# 01_MAIN.net
KiCad netlist of a schematic drawn in Altium Designer
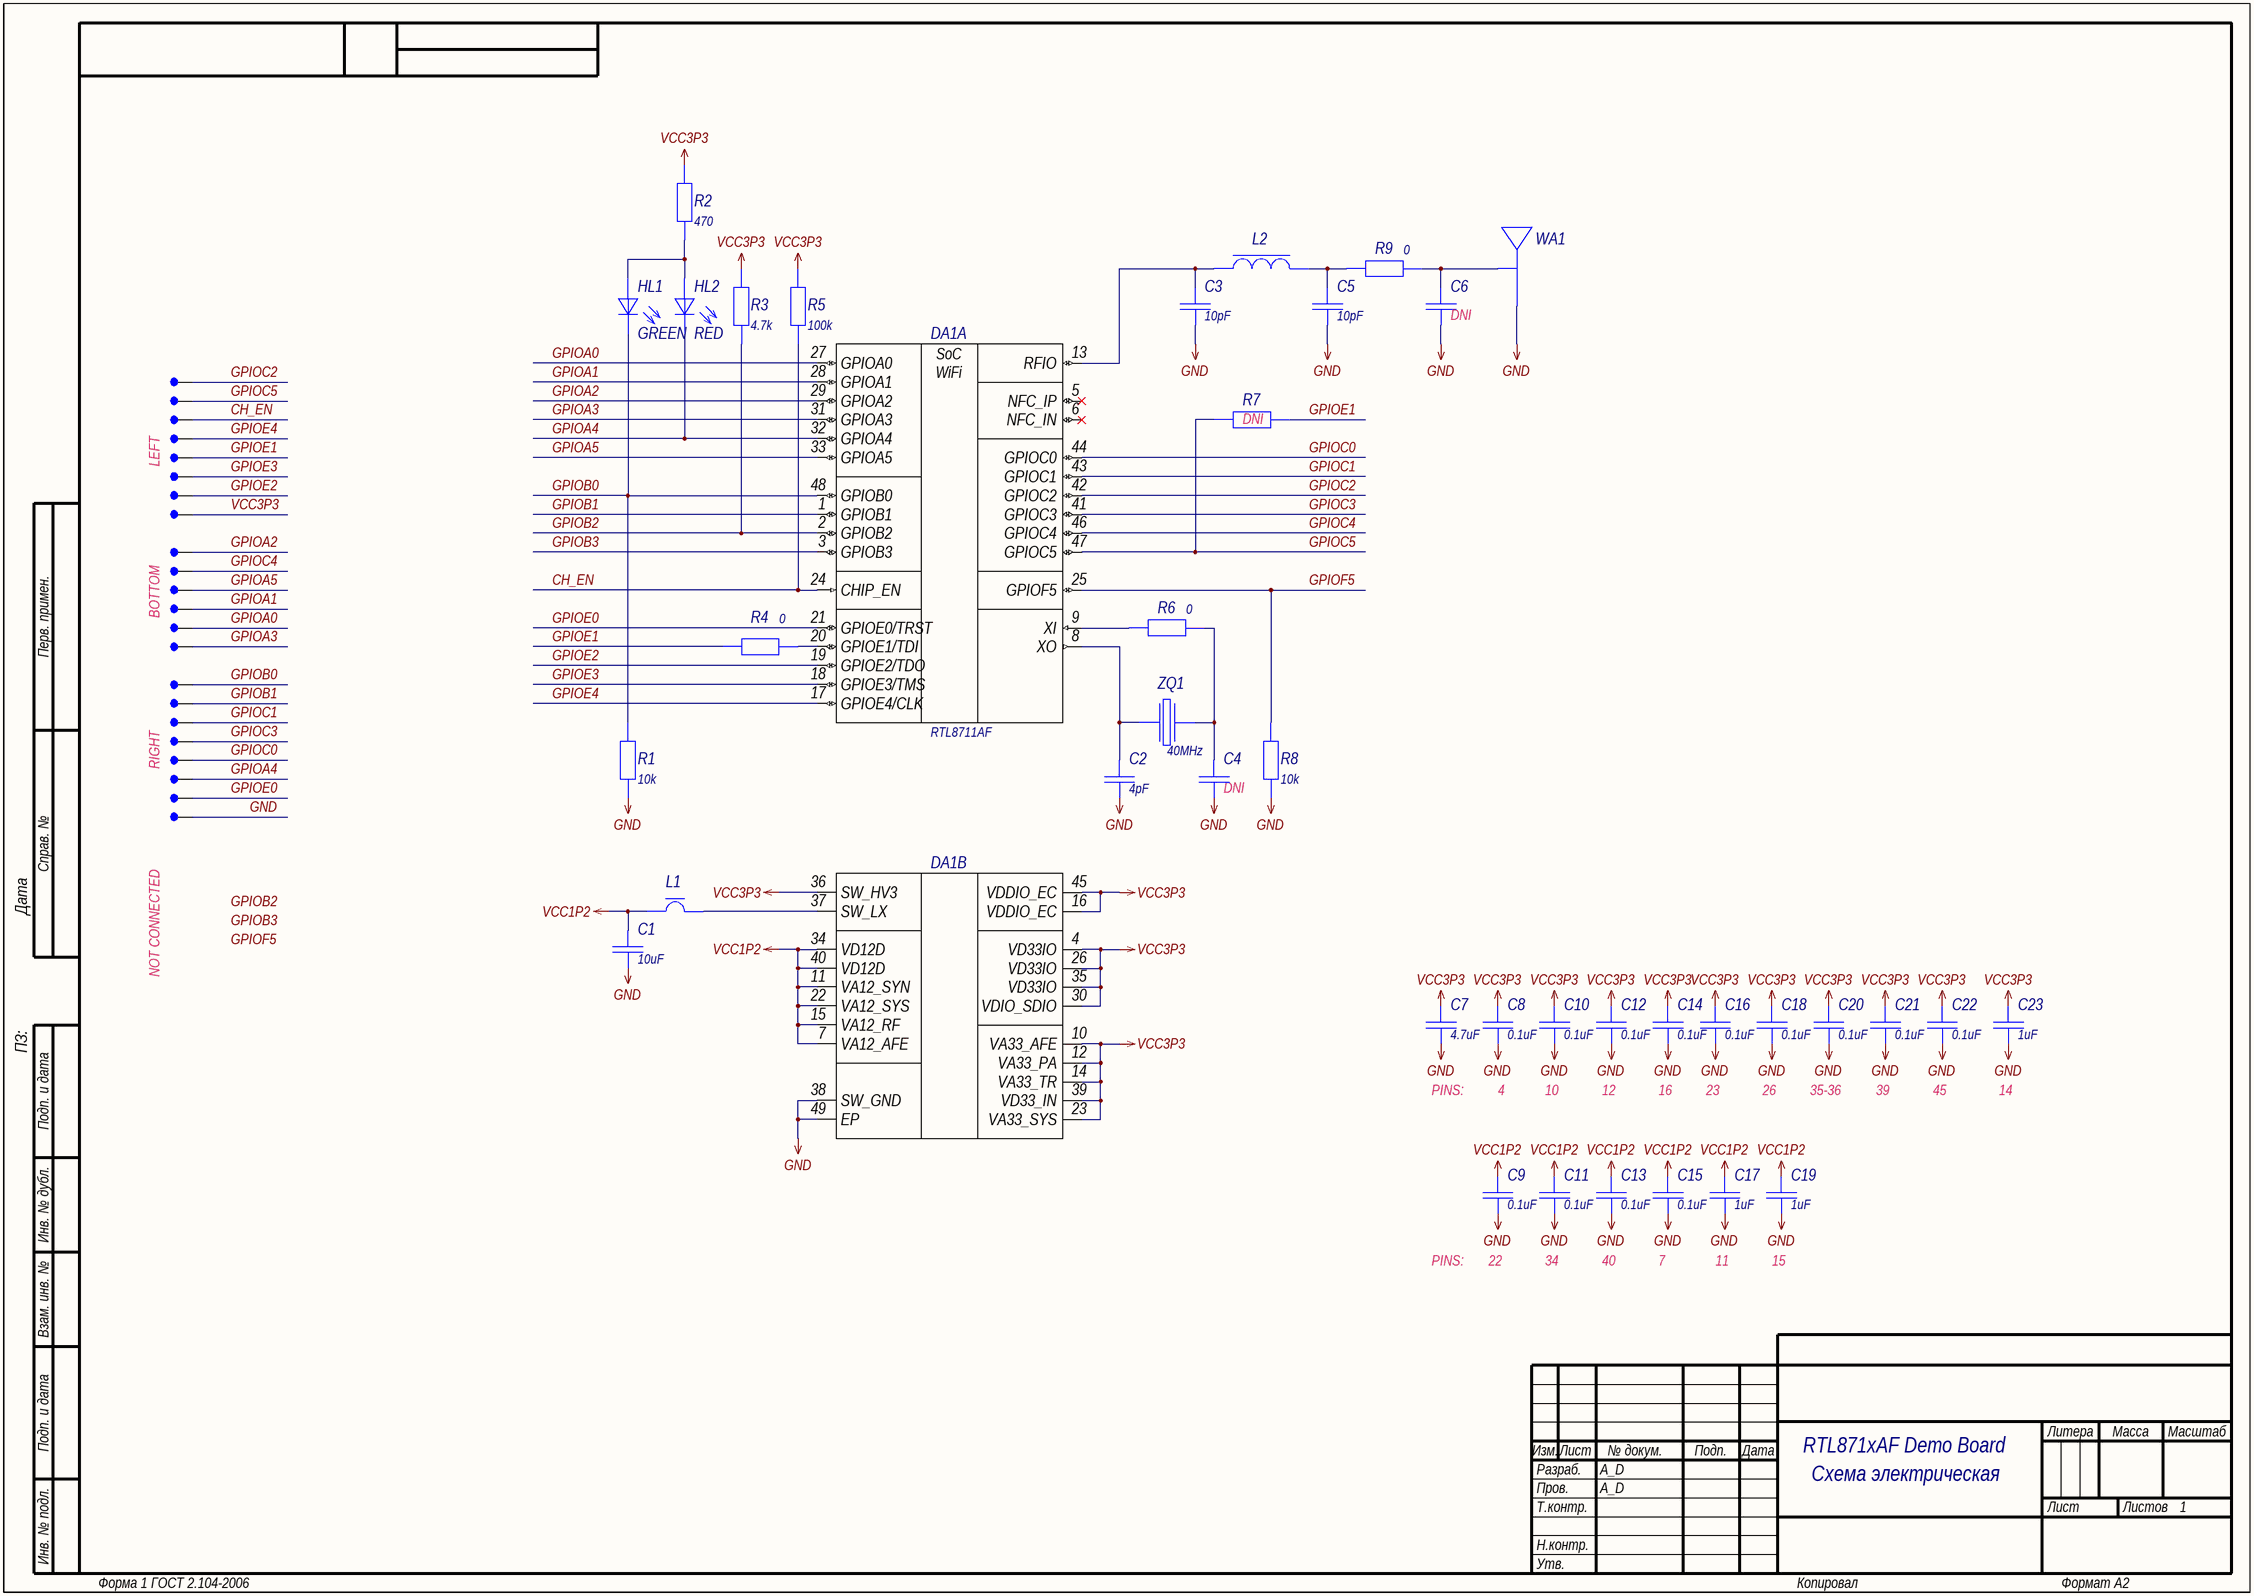
[diagram p0: 01_MAIN.SchDoc]

(export (version "E")
  (design (tool "Eeschema 10.0.6"))
  (components
    (comp (ref "C1")
      (value "10uF")
      (footprint "C0603_L")
      (fields
        (field (name "PART NUMBER") "GRM188R60J106ME47D")
        (field (name "VOLTAGE") "6.3V")
        (field (name "TOLERANCE") "±20%")
        (field (name "PUBLISHER") "Andrew Danich")
      )
      (libsource (lib "Lib_IMP_GOST") (part "Capacitor"))
    )
    (comp (ref "C2")
      (value "4pF")
      (footprint "C0402_L")
      (fields
        (field (name "PART NUMBER") "GRM1555C1H4R0CZ01D")
        (field (name "VOLTAGE") "50V")
        (field (name "TOLERANCE") "±0.25pF")
        (field (name "PUBLISHER") "Andrew Danich")
      )
      (libsource (lib "Lib_IMP_GOST") (part "Capacitor"))
    )
    (comp (ref "C3")
      (value "10pF")
      (footprint "C0402_L")
      (fields
        (field (name "PART NUMBER") "GRM1555C1H100JA01D")
        (field (name "VOLTAGE") "50V")
        (field (name "TOLERANCE") "±5%")
        (field (name "PUBLISHER") "Andrew Danich")
      )
      (libsource (lib "Lib_IMP_GOST") (part "Capacitor"))
    )
    (comp (ref "C4")
      (value "Capacitor")
      (footprint "C0402_L")
      (fields
        (field (name "PART NUMBER") "GRM1555C1H4R0CZ01D")
        (field (name "VOLTAGE") "50V")
        (field (name "TOLERANCE") "±0.25pF")
        (field (name "PUBLISHER") "Andrew Danich")
      )
      (libsource (lib "Lib_IMP_GOST") (part "Capacitor"))
    )
    (comp (ref "C5")
      (value "10pF")
      (footprint "C0402_L")
      (fields
        (field (name "PART NUMBER") "GRM1555C1H100JA01D")
        (field (name "VOLTAGE") "50V")
        (field (name "TOLERANCE") "±5%")
        (field (name "PUBLISHER") "Andrew Danich")
      )
      (libsource (lib "Lib_IMP_GOST") (part "Capacitor"))
    )
    (comp (ref "C6")
      (value "Capacitor")
      (footprint "C0402_L")
      (fields
        (field (name "PART NUMBER") "GRM1555C1H100JA01D")
        (field (name "VOLTAGE") "50V")
        (field (name "TOLERANCE") "±5%")
        (field (name "PUBLISHER") "Andrew Danich")
      )
      (libsource (lib "Lib_IMP_GOST") (part "Capacitor"))
    )
    (comp (ref "C7")
      (value "4.7uF")
      (footprint "C0603_L")
      (fields
        (field (name "PART NUMBER") "GRM188R61A475KE15D")
        (field (name "VOLTAGE") "10V")
        (field (name "TOLERANCE") "±10%")
        (field (name "PUBLISHER") "Andrew Danich")
      )
      (libsource (lib "Lib_IMP_GOST") (part "Capacitor"))
    )
    (comp (ref "C8")
      (value "0.1uF")
      (footprint "C0402_L")
      (fields
        (field (name "PART NUMBER") "GRM155R71A104KA01D")
        (field (name "VOLTAGE") "10V")
        (field (name "TOLERANCE") "±10%")
        (field (name "PUBLISHER") "Andrew Danich")
      )
      (libsource (lib "Lib_IMP_GOST") (part "Capacitor"))
    )
    (comp (ref "C9")
      (value "0.1uF")
      (footprint "C0402_L")
      (fields
        (field (name "PART NUMBER") "GRM155R71A104KA01D")
        (field (name "VOLTAGE") "10V")
        (field (name "TOLERANCE") "±10%")
        (field (name "PUBLISHER") "Andrew Danich")
      )
      (libsource (lib "Lib_IMP_GOST") (part "Capacitor"))
    )
    (comp (ref "C10")
      (value "0.1uF")
      (footprint "C0402_L")
      (fields
        (field (name "PART NUMBER") "GRM155R71A104KA01D")
        (field (name "VOLTAGE") "10V")
        (field (name "TOLERANCE") "±10%")
        (field (name "PUBLISHER") "Andrew Danich")
      )
      (libsource (lib "Lib_IMP_GOST") (part "Capacitor"))
    )
    (comp (ref "C11")
      (value "0.1uF")
      (footprint "C0402_L")
      (fields
        (field (name "PART NUMBER") "GRM155R71A104KA01D")
        (field (name "VOLTAGE") "10V")
        (field (name "TOLERANCE") "±10%")
        (field (name "PUBLISHER") "Andrew Danich")
      )
      (libsource (lib "Lib_IMP_GOST") (part "Capacitor"))
    )
    (comp (ref "C12")
      (value "0.1uF")
      (footprint "C0402_L")
      (fields
        (field (name "PART NUMBER") "GRM155R71A104KA01D")
        (field (name "VOLTAGE") "10V")
        (field (name "TOLERANCE") "±10%")
        (field (name "PUBLISHER") "Andrew Danich")
      )
      (libsource (lib "Lib_IMP_GOST") (part "Capacitor"))
    )
    (comp (ref "C13")
      (value "0.1uF")
      (footprint "C0402_L")
      (fields
        (field (name "PART NUMBER") "GRM155R71A104KA01D")
        (field (name "VOLTAGE") "10V")
        (field (name "TOLERANCE") "±10%")
        (field (name "PUBLISHER") "Andrew Danich")
      )
      (libsource (lib "Lib_IMP_GOST") (part "Capacitor"))
    )
    (comp (ref "C14")
      (value "0.1uF")
      (footprint "C0402_L")
      (fields
        (field (name "PART NUMBER") "GRM155R71A104KA01D")
        (field (name "VOLTAGE") "10V")
        (field (name "TOLERANCE") "±10%")
        (field (name "PUBLISHER") "Andrew Danich")
      )
      (libsource (lib "Lib_IMP_GOST") (part "Capacitor"))
    )
    (comp (ref "C15")
      (value "0.1uF")
      (footprint "C0402_L")
      (fields
        (field (name "PART NUMBER") "GRM155R71A104KA01D")
        (field (name "VOLTAGE") "10V")
        (field (name "TOLERANCE") "±10%")
        (field (name "PUBLISHER") "Andrew Danich")
      )
      (libsource (lib "Lib_IMP_GOST") (part "Capacitor"))
    )
    (comp (ref "C16")
      (value "0.1uF")
      (footprint "C0402_L")
      (fields
        (field (name "PART NUMBER") "GRM155R71A104KA01D")
        (field (name "VOLTAGE") "10V")
        (field (name "TOLERANCE") "±10%")
        (field (name "PUBLISHER") "Andrew Danich")
      )
      (libsource (lib "Lib_IMP_GOST") (part "Capacitor"))
    )
    (comp (ref "C17")
      (value "1uF")
      (footprint "C0402_L")
      (fields
        (field (name "PART NUMBER") "GRM155R61A105KE15D")
        (field (name "VOLTAGE") "10V")
        (field (name "TOLERANCE") "±10%")
        (field (name "PUBLISHER") "Andrew Danich")
      )
      (libsource (lib "Lib_IMP_GOST") (part "Capacitor"))
    )
    (comp (ref "C18")
      (value "0.1uF")
      (footprint "C0402_L")
      (fields
        (field (name "PART NUMBER") "GRM155R71A104KA01D")
        (field (name "VOLTAGE") "10V")
        (field (name "TOLERANCE") "±10%")
        (field (name "PUBLISHER") "Andrew Danich")
      )
      (libsource (lib "Lib_IMP_GOST") (part "Capacitor"))
    )
    (comp (ref "C19")
      (value "1uF")
      (footprint "C0402_L")
      (fields
        (field (name "PART NUMBER") "GRM155R61A105KE15D")
        (field (name "VOLTAGE") "10V")
        (field (name "TOLERANCE") "±10%")
        (field (name "PUBLISHER") "Andrew Danich")
      )
      (libsource (lib "Lib_IMP_GOST") (part "Capacitor"))
    )
    (comp (ref "C20")
      (value "0.1uF")
      (footprint "C0402_L")
      (fields
        (field (name "PART NUMBER") "GRM155R71A104KA01D")
        (field (name "VOLTAGE") "10V")
        (field (name "TOLERANCE") "±10%")
        (field (name "PUBLISHER") "Andrew Danich")
      )
      (libsource (lib "Lib_IMP_GOST") (part "Capacitor"))
    )
    (comp (ref "C21")
      (value "0.1uF")
      (footprint "C0402_L")
      (fields
        (field (name "PART NUMBER") "GRM155R71A104KA01D")
        (field (name "VOLTAGE") "10V")
        (field (name "TOLERANCE") "±10%")
        (field (name "PUBLISHER") "Andrew Danich")
      )
      (libsource (lib "Lib_IMP_GOST") (part "Capacitor"))
    )
    (comp (ref "C22")
      (value "0.1uF")
      (footprint "C0402_L")
      (fields
        (field (name "PART NUMBER") "GRM155R71A104KA01D")
        (field (name "VOLTAGE") "10V")
        (field (name "TOLERANCE") "±10%")
        (field (name "PUBLISHER") "Andrew Danich")
      )
      (libsource (lib "Lib_IMP_GOST") (part "Capacitor"))
    )
    (comp (ref "C23")
      (value "1uF")
      (footprint "C0402_L")
      (fields
        (field (name "PART NUMBER") "GRM155R61A105KE15D")
        (field (name "VOLTAGE") "10V")
        (field (name "TOLERANCE") "±10%")
        (field (name "PUBLISHER") "Andrew Danich")
      )
      (libsource (lib "Lib_IMP_GOST") (part "Capacitor"))
    )
    (comp (ref "DA1")
      (value "RTL8711AF")
      (footprint "QFN-48-6x6")
      (fields
        (field (name "MANUFACTURER") "Realtek")
        (field (name "Comment") "RTL871xAF")
        (field (name "PART NUMBER") "RTL8711AF")
        (field (name "PUBLISHER") "Andrew Danich")
      )
      (libsource (lib "Lib_IMP_GOST") (part "RTL871xAF"))
    )
    (comp (ref "HL1")
      (value "GREEN")
      (footprint "LD0402_L")
      (fields
        (field (name "PART NUMBER") "KPHHS-1005MGCK")
        (field (name "MANUFACTURER") "Kingbright")
        (field (name "PUBLISHER") "Andrew Danich")
      )
      (libsource (lib "Lib_IMP_GOST") (part "Led-1"))
    )
    (comp (ref "HL2")
      (value "RED")
      (footprint "LD0402_L")
      (fields
        (field (name "PART NUMBER") "KPHHS-1005QBC-D-V")
        (field (name "MANUFACTURER") "Kingbright")
        (field (name "PUBLISHER") "Andrew Danich")
      )
      (libsource (lib "Lib_IMP_GOST") (part "Led-1"))
    )
    (comp (ref "L1")
      (value "FerriteBead")
      (footprint "L0805_L")
      (fields
        (field (name "PART NUMBER") "BLM21PG331SN1")
        (field (name "MANUFACTURER") "Murata")
        (field (name "PUBLISHER") "Andrew Danich")
      )
      (libsource (lib "Lib_IMP_GOST") (part "FerriteBead"))
    )
    (comp (ref "L2")
      (value "Coil")
      (footprint "L0402_L")
      (fields
        (field (name "PART NUMBER") "LQG15HS2N2S02D")
        (field (name "TOLERANCE") "±0.3nH")
        (field (name "MANUFACTURER") "Murata")
        (field (name "PUBLISHER") "Andrew Danich")
      )
      (libsource (lib "Lib_IMP_GOST") (part "Coil"))
    )
    (comp (ref "R1")
      (value "10k")
      (footprint "R0402_L")
      (fields
        (field (name "PART NUMBER") "RC0402FR-0710KL")
        (field (name "TOLERANCE") "±1%")
        (field (name "MANUFACTURER") "Yageo")
        (field (name "PUBLISHER") "Andrew Danich")
      )
      (libsource (lib "Lib_IMP_GOST") (part "Resistor"))
    )
    (comp (ref "R2")
      (value "470")
      (footprint "R0402_L")
      (fields
        (field (name "PART NUMBER") "RC0402JR-07430RL")
        (field (name "TOLERANCE") "±5%")
        (field (name "MANUFACTURER") "Yageo")
        (field (name "PUBLISHER") "Andrew Danich")
      )
      (libsource (lib "Lib_IMP_GOST") (part "Resistor"))
    )
    (comp (ref "R3")
      (value "4.7k")
      (footprint "R0402_L")
      (fields
        (field (name "PART NUMBER") "RC0402JR-074K7L")
        (field (name "TOLERANCE") "±5%")
        (field (name "MANUFACTURER") "Yageo")
        (field (name "PUBLISHER") "Andrew Danich")
      )
      (libsource (lib "Lib_IMP_GOST") (part "Resistor"))
    )
    (comp (ref "R4")
      (value "0")
      (footprint "R0402_L")
      (fields
        (field (name "PART NUMBER") "RC0402JR-070RL")
        (field (name "TOLERANCE") "±1%")
        (field (name "MANUFACTURER") "Yageo")
        (field (name "PUBLISHER") "Andrew Danich")
      )
      (libsource (lib "Lib_IMP_GOST") (part "Resistor"))
    )
    (comp (ref "R5")
      (value "100k")
      (footprint "R0402_L")
      (fields
        (field (name "PART NUMBER") "RC0402JR-07100KL")
        (field (name "TOLERANCE") "±5%")
        (field (name "MANUFACTURER") "Yageo")
        (field (name "PUBLISHER") "Andrew Danich")
      )
      (libsource (lib "Lib_IMP_GOST") (part "Resistor"))
    )
    (comp (ref "R6")
      (value "0")
      (footprint "R0402_L")
      (fields
        (field (name "PART NUMBER") "RC0402JR-070RL")
        (field (name "TOLERANCE") "±1%")
        (field (name "MANUFACTURER") "Yageo")
        (field (name "PUBLISHER") "Andrew Danich")
      )
      (libsource (lib "Lib_IMP_GOST") (part "Resistor"))
    )
    (comp (ref "R7")
      (value "Resistor")
      (footprint "R0402_L")
      (fields
        (field (name "PART NUMBER") "RC0402JR-070RL")
        (field (name "TOLERANCE") "±1%")
        (field (name "MANUFACTURER") "Yageo")
        (field (name "PUBLISHER") "Andrew Danich")
      )
      (libsource (lib "Lib_IMP_GOST") (part "Resistor"))
    )
    (comp (ref "R8")
      (value "10k")
      (footprint "R0402_L")
      (fields
        (field (name "PART NUMBER") "RC0402FR-0710KL")
        (field (name "TOLERANCE") "±1%")
        (field (name "MANUFACTURER") "Yageo")
        (field (name "PUBLISHER") "Andrew Danich")
      )
      (libsource (lib "Lib_IMP_GOST") (part "Resistor"))
    )
    (comp (ref "R9")
      (value "0")
      (footprint "R0402_L")
      (fields
        (field (name "PART NUMBER") "RC0402JR-070RL")
        (field (name "TOLERANCE") "±1%")
        (field (name "MANUFACTURER") "Yageo")
        (field (name "PUBLISHER") "Andrew Danich")
      )
      (libsource (lib "Lib_IMP_GOST") (part "Resistor"))
    )
    (comp (ref "WA1")
      (value "Antenna_PCB_2p")
      (footprint "PCB-AN043")
      (fields
        (field (name "PART NUMBER") "PCB-AN043")
        (field (name "MANUFACTURER") "Texas Instruments")
        (field (name "PUBLISHER") "Andrew Danich")
      )
      (libsource (lib "Lib_IMP_GOST") (part "Antenna_PCB_2p"))
    )
    (comp (ref "XS1") (value "PCB-SPIN") (footprint "PCB-SPIN") (libsource (lib "Schlib") (part "PCB-SPIN")))
    (comp (ref "XS2") (value "PCB-SPIN") (footprint "PCB-SPIN") (libsource (lib "Schlib") (part "PCB-SPIN")))
    (comp (ref "XS3") (value "PCB-SPIN") (footprint "PCB-SPIN") (libsource (lib "Schlib") (part "PCB-SPIN")))
    (comp (ref "XS4") (value "PCB-SPIN") (footprint "PCB-SPIN") (libsource (lib "Schlib") (part "PCB-SPIN")))
    (comp (ref "XS5") (value "PCB-SPIN") (footprint "PCB-SPIN") (libsource (lib "Schlib") (part "PCB-SPIN")))
    (comp (ref "XS6") (value "PCB-SPIN") (footprint "PCB-SPIN") (libsource (lib "Schlib") (part "PCB-SPIN")))
    (comp (ref "XS7") (value "PCB-SPIN") (footprint "PCB-SPIN") (libsource (lib "Schlib") (part "PCB-SPIN")))
    (comp (ref "XS8") (value "PCB-SPIN") (footprint "PCB-SPIN") (libsource (lib "Schlib") (part "PCB-SPIN")))
    (comp (ref "XS9") (value "PCB-SPIN") (footprint "PCB-SPIN") (libsource (lib "Schlib") (part "PCB-SPIN")))
    (comp (ref "XS10") (value "PCB-SPIN") (footprint "PCB-SPIN") (libsource (lib "Schlib") (part "PCB-SPIN")))
    (comp (ref "XS11") (value "PCB-SPIN") (footprint "PCB-SPIN") (libsource (lib "Schlib") (part "PCB-SPIN")))
    (comp (ref "XS12") (value "PCB-SPIN") (footprint "PCB-SPIN") (libsource (lib "Schlib") (part "PCB-SPIN")))
    (comp (ref "XS13") (value "PCB-SPIN") (footprint "PCB-SPIN") (libsource (lib "Schlib") (part "PCB-SPIN")))
    (comp (ref "XS14") (value "PCB-SPIN") (footprint "PCB-SPIN") (libsource (lib "Schlib") (part "PCB-SPIN")))
    (comp (ref "XS15") (value "PCB-SPIN") (footprint "PCB-SPIN") (libsource (lib "Schlib") (part "PCB-SPIN")))
    (comp (ref "XS16") (value "PCB-SPIN") (footprint "PCB-SPIN") (libsource (lib "Schlib") (part "PCB-SPIN")))
    (comp (ref "XS17") (value "PCB-SPIN") (footprint "PCB-SPIN") (libsource (lib "Schlib") (part "PCB-SPIN")))
    (comp (ref "XS18") (value "PCB-SPIN") (footprint "PCB-SPIN") (libsource (lib "Schlib") (part "PCB-SPIN")))
    (comp (ref "XS19") (value "PCB-SPIN") (footprint "PCB-SPIN") (libsource (lib "Schlib") (part "PCB-SPIN")))
    (comp (ref "XS20") (value "PCB-SPIN") (footprint "PCB-SPIN") (libsource (lib "Schlib") (part "PCB-SPIN")))
    (comp (ref "XS21") (value "PCB-SPIN") (footprint "PCB-SPIN") (libsource (lib "Schlib") (part "PCB-SPIN")))
    (comp (ref "XS22") (value "PCB-SPIN") (footprint "PCB-SPIN") (libsource (lib "Schlib") (part "PCB-SPIN")))
    (comp (ref "ZQ1")
      (value "Crystal")
      (footprint "SX-2520")
      (fields
        (field (name "PART NUMBER") "CX2520DB40000D0FLJCC")
        (field (name "OUTPUT FREQUENCY") "40MHz")
        (field (name "MANUFACTURER") "AVX / Kyocera")
        (field (name "PUBLISHER") "Andrew Danich")
      )
      (libsource (lib "Lib_IMP_GOST") (part "Crystal"))
    )
  )
  (nets
    (net (code "1") (name "/CH_EN") (class "Default")
      (node (ref "DA1") (pin "24") (pinfunction "CHIP_EN_24") (pintype "input"))
      (node (ref "R5") (pin "1") (pinfunction "1_1") (pintype "passive"))
      (node (ref "XS3") (pin "1") (pinfunction "1_1") (pintype "passive"))
    )
    (net (code "2") (name "/GPIOA0") (class "Default")
      (node (ref "DA1") (pin "27") (pinfunction "GPIOA0_27") (pintype "bidirectional"))
      (node (ref "XS13") (pin "1") (pinfunction "1_1") (pintype "passive"))
    )
    (net (code "3") (name "/GPIOA1") (class "Default")
      (node (ref "DA1") (pin "28") (pinfunction "GPIOA1_28") (pintype "bidirectional"))
      (node (ref "XS12") (pin "1") (pinfunction "1_1") (pintype "passive"))
    )
    (net (code "4") (name "/GPIOA2") (class "Default")
      (node (ref "DA1") (pin "29") (pinfunction "GPIOA2_29") (pintype "bidirectional"))
      (node (ref "XS9") (pin "1") (pinfunction "1_1") (pintype "passive"))
    )
    (net (code "5") (name "/GPIOA3") (class "Default")
      (node (ref "DA1") (pin "31") (pinfunction "GPIOA3_31") (pintype "bidirectional"))
      (node (ref "XS14") (pin "1") (pinfunction "1_1") (pintype "passive"))
    )
    (net (code "6") (name "/GPIOA4") (class "Default")
      (node (ref "DA1") (pin "32") (pinfunction "GPIOA4_32") (pintype "bidirectional"))
      (node (ref "HL2") (pin "2") (pinfunction "К_2") (pintype "passive"))
      (node (ref "XS20") (pin "1") (pinfunction "1_1") (pintype "passive"))
    )
    (net (code "7") (name "/GPIOA5") (class "Default")
      (node (ref "DA1") (pin "33") (pinfunction "GPIOA5_33") (pintype "bidirectional"))
      (node (ref "XS11") (pin "1") (pinfunction "1_1") (pintype "passive"))
    )
    (net (code "8") (name "/GPIOB0") (class "Default")
      (node (ref "DA1") (pin "48") (pinfunction "GPIOB0_48") (pintype "bidirectional"))
      (node (ref "HL1") (pin "2") (pinfunction "К_2") (pintype "passive"))
      (node (ref "R1") (pin "2") (pinfunction "2_2") (pintype "passive"))
      (node (ref "XS15") (pin "1") (pinfunction "1_1") (pintype "passive"))
    )
    (net (code "9") (name "/GPIOB1") (class "Default")
      (node (ref "DA1") (pin "1") (pinfunction "GPIOB1_1") (pintype "bidirectional"))
      (node (ref "XS16") (pin "1") (pinfunction "1_1") (pintype "passive"))
    )
    (net (code "10") (name "/GPIOB2") (class "Default")
      (node (ref "DA1") (pin "2") (pinfunction "GPIOB2_2") (pintype "bidirectional"))
      (node (ref "R3") (pin "1") (pinfunction "1_1") (pintype "passive"))
    )
    (net (code "11") (name "/GPIOB3") (class "Default")
      (node (ref "DA1") (pin "3") (pinfunction "GPIOB3_3") (pintype "bidirectional"))
    )
    (net (code "12") (name "/GPIOC0") (class "Default")
      (node (ref "DA1") (pin "44") (pinfunction "GPIOC0_44") (pintype "bidirectional"))
      (node (ref "XS19") (pin "1") (pinfunction "1_1") (pintype "passive"))
    )
    (net (code "13") (name "/GPIOC1") (class "Default")
      (node (ref "DA1") (pin "43") (pinfunction "GPIOC1_43") (pintype "bidirectional"))
      (node (ref "XS17") (pin "1") (pinfunction "1_1") (pintype "passive"))
    )
    (net (code "14") (name "/GPIOC2") (class "Default")
      (node (ref "DA1") (pin "42") (pinfunction "GPIOC2_42") (pintype "bidirectional"))
      (node (ref "XS1") (pin "1") (pinfunction "1_1") (pintype "passive"))
    )
    (net (code "15") (name "/GPIOC3") (class "Default")
      (node (ref "DA1") (pin "41") (pinfunction "GPIOC3_41") (pintype "bidirectional"))
      (node (ref "XS18") (pin "1") (pinfunction "1_1") (pintype "passive"))
    )
    (net (code "16") (name "/GPIOC4") (class "Default")
      (node (ref "DA1") (pin "46") (pinfunction "GPIOC4_46") (pintype "bidirectional"))
      (node (ref "XS10") (pin "1") (pinfunction "1_1") (pintype "passive"))
    )
    (net (code "17") (name "/GPIOC5") (class "Default")
      (node (ref "DA1") (pin "47") (pinfunction "GPIOC5_47") (pintype "bidirectional"))
      (node (ref "R7") (pin "1") (pinfunction "1_1") (pintype "passive"))
      (node (ref "XS2") (pin "1") (pinfunction "1_1") (pintype "passive"))
    )
    (net (code "18") (name "/GPIOE0") (class "Default")
      (node (ref "DA1") (pin "21") (pinfunction "GPIOE0/TRST_21") (pintype "bidirectional"))
      (node (ref "XS21") (pin "1") (pinfunction "1_1") (pintype "passive"))
    )
    (net (code "19") (name "/GPIOE1") (class "Default")
      (node (ref "R4") (pin "1") (pinfunction "1_1") (pintype "passive"))
      (node (ref "R7") (pin "2") (pinfunction "2_2") (pintype "passive"))
      (node (ref "XS5") (pin "1") (pinfunction "1_1") (pintype "passive"))
    )
    (net (code "20") (name "/GPIOE2") (class "Default")
      (node (ref "DA1") (pin "19") (pinfunction "GPIOE2/TDO_19") (pintype "bidirectional"))
      (node (ref "XS7") (pin "1") (pinfunction "1_1") (pintype "passive"))
    )
    (net (code "21") (name "/GPIOE3") (class "Default")
      (node (ref "DA1") (pin "18") (pinfunction "GPIOE3/TMS_18") (pintype "bidirectional"))
      (node (ref "XS6") (pin "1") (pinfunction "1_1") (pintype "passive"))
    )
    (net (code "22") (name "/GPIOE4") (class "Default")
      (node (ref "DA1") (pin "17") (pinfunction "GPIOE4/CLK_17") (pintype "bidirectional"))
      (node (ref "XS4") (pin "1") (pinfunction "1_1") (pintype "passive"))
    )
    (net (code "23") (name "/GPIOF5") (class "Default")
      (node (ref "DA1") (pin "25") (pinfunction "GPIOF5_25") (pintype "bidirectional"))
      (node (ref "R8") (pin "2") (pinfunction "2_2") (pintype "passive"))
    )
    (net (code "24") (name "GND") (class "Default")
      (node (ref "C1") (pin "1") (pinfunction "1_1") (pintype "passive"))
      (node (ref "C10") (pin "1") (pinfunction "1_1") (pintype "passive"))
      (node (ref "C11") (pin "1") (pinfunction "1_1") (pintype "passive"))
      (node (ref "C12") (pin "1") (pinfunction "1_1") (pintype "passive"))
      (node (ref "C13") (pin "1") (pinfunction "1_1") (pintype "passive"))
      (node (ref "C14") (pin "1") (pinfunction "1_1") (pintype "passive"))
      (node (ref "C15") (pin "1") (pinfunction "1_1") (pintype "passive"))
      (node (ref "C16") (pin "1") (pinfunction "1_1") (pintype "passive"))
      (node (ref "C17") (pin "1") (pinfunction "1_1") (pintype "passive"))
      (node (ref "C18") (pin "1") (pinfunction "1_1") (pintype "passive"))
      (node (ref "C19") (pin "1") (pinfunction "1_1") (pintype "passive"))
      (node (ref "C2") (pin "1") (pinfunction "1_1") (pintype "passive"))
      (node (ref "C20") (pin "1") (pinfunction "1_1") (pintype "passive"))
      (node (ref "C21") (pin "1") (pinfunction "1_1") (pintype "passive"))
      (node (ref "C22") (pin "1") (pinfunction "1_1") (pintype "passive"))
      (node (ref "C23") (pin "1") (pinfunction "1_1") (pintype "passive"))
      (node (ref "C3") (pin "1") (pinfunction "1_1") (pintype "passive"))
      (node (ref "C4") (pin "1") (pinfunction "1_1") (pintype "passive"))
      (node (ref "C5") (pin "1") (pinfunction "1_1") (pintype "passive"))
      (node (ref "C6") (pin "1") (pinfunction "1_1") (pintype "passive"))
      (node (ref "C7") (pin "1") (pinfunction "1_1") (pintype "passive"))
      (node (ref "C8") (pin "1") (pinfunction "1_1") (pintype "passive"))
      (node (ref "C9") (pin "1") (pinfunction "1_1") (pintype "passive"))
      (node (ref "DA1") (pin "38") (pinfunction "SW_GND_38") (pintype "power_in"))
      (node (ref "DA1") (pin "49") (pinfunction "EP_49") (pintype "power_in"))
      (node (ref "R1") (pin "1") (pinfunction "1_1") (pintype "passive"))
      (node (ref "R8") (pin "1") (pinfunction "1_1") (pintype "passive"))
      (node (ref "WA1") (pin "2") (pinfunction "2_2") (pintype "passive"))
      (node (ref "XS22") (pin "1") (pinfunction "1_1") (pintype "passive"))
    )
    (net (code "25") (name "Net-(C4-Pad2)") (class "Default")
      (node (ref "C4") (pin "2") (pinfunction "2_2") (pintype "passive"))
      (node (ref "R6") (pin "2") (pinfunction "2_2") (pintype "passive"))
      (node (ref "ZQ1") (pin "3") (pinfunction "3_3") (pintype "passive"))
    )
    (net (code "26") (name "Net-(C5-Pad2)") (class "Default")
      (node (ref "C5") (pin "2") (pinfunction "2_2") (pintype "passive"))
      (node (ref "L2") (pin "2") (pinfunction "2_2") (pintype "passive"))
      (node (ref "R9") (pin "1") (pinfunction "1_1") (pintype "passive"))
    )
    (net (code "27") (name "Net-(C6-Pad2)") (class "Default")
      (node (ref "C6") (pin "2") (pinfunction "2_2") (pintype "passive"))
      (node (ref "R9") (pin "2") (pinfunction "2_2") (pintype "passive"))
      (node (ref "WA1") (pin "1") (pinfunction "1_1") (pintype "passive"))
    )
    (net (code "28") (name "Net-(DA1A-GPIOE1{slash}TDI)") (class "Default")
      (node (ref "DA1") (pin "20") (pinfunction "GPIOE1/TDI_20") (pintype "bidirectional"))
      (node (ref "R4") (pin "2") (pinfunction "2_2") (pintype "passive"))
    )
    (net (code "29") (name "Net-(DA1A-RFIO)") (class "Default")
      (node (ref "C3") (pin "2") (pinfunction "2_2") (pintype "passive"))
      (node (ref "DA1") (pin "13") (pinfunction "RFIO_13") (pintype "bidirectional"))
      (node (ref "L2") (pin "1") (pinfunction "1_1") (pintype "passive"))
    )
    (net (code "30") (name "Net-(DA1A-XI)") (class "Default")
      (node (ref "DA1") (pin "9") (pinfunction "XI_9") (pintype "input"))
      (node (ref "R6") (pin "1") (pinfunction "1_1") (pintype "passive"))
    )
    (net (code "31") (name "Net-(DA1A-XO)") (class "Default")
      (node (ref "C2") (pin "2") (pinfunction "2_2") (pintype "passive"))
      (node (ref "DA1") (pin "8") (pinfunction "XO_8") (pintype "output"))
      (node (ref "ZQ1") (pin "1") (pinfunction "1_1") (pintype "passive"))
    )
    (net (code "32") (name "Net-(DA1B-SW_LX)") (class "Default")
      (node (ref "DA1") (pin "37") (pinfunction "SW_LX_37") (pintype "power_in"))
      (node (ref "L1") (pin "2") (pinfunction "2_2") (pintype "passive"))
    )
    (net (code "33") (name "Net-(HL1-А)") (class "Default")
      (node (ref "HL1") (pin "1") (pinfunction "А_1") (pintype "passive"))
      (node (ref "HL2") (pin "1") (pinfunction "А_1") (pintype "passive"))
      (node (ref "R2") (pin "1") (pinfunction "1_1") (pintype "passive"))
    )
    (net (code "34") (name "VCC1P2") (class "Default")
      (node (ref "C1") (pin "2") (pinfunction "2_2") (pintype "passive"))
      (node (ref "C11") (pin "2") (pinfunction "2_2") (pintype "passive"))
      (node (ref "C13") (pin "2") (pinfunction "2_2") (pintype "passive"))
      (node (ref "C15") (pin "2") (pinfunction "2_2") (pintype "passive"))
      (node (ref "C17") (pin "2") (pinfunction "2_2") (pintype "passive"))
      (node (ref "C19") (pin "2") (pinfunction "2_2") (pintype "passive"))
      (node (ref "C9") (pin "2") (pinfunction "2_2") (pintype "passive"))
      (node (ref "DA1") (pin "11") (pinfunction "VA12_SYN_11") (pintype "power_in"))
      (node (ref "DA1") (pin "15") (pinfunction "VA12_RF_15") (pintype "power_in"))
      (node (ref "DA1") (pin "22") (pinfunction "VA12_SYS_22") (pintype "power_in"))
      (node (ref "DA1") (pin "34") (pinfunction "VD12D_34") (pintype "power_in"))
      (node (ref "DA1") (pin "40") (pinfunction "VD12D_40") (pintype "power_in"))
      (node (ref "DA1") (pin "7") (pinfunction "VA12_AFE_7") (pintype "power_in"))
      (node (ref "L1") (pin "1") (pinfunction "1_1") (pintype "passive"))
    )
    (net (code "35") (name "VCC3P3") (class "Default")
      (node (ref "C10") (pin "2") (pinfunction "2_2") (pintype "passive"))
      (node (ref "C12") (pin "2") (pinfunction "2_2") (pintype "passive"))
      (node (ref "C14") (pin "2") (pinfunction "2_2") (pintype "passive"))
      (node (ref "C16") (pin "2") (pinfunction "2_2") (pintype "passive"))
      (node (ref "C18") (pin "2") (pinfunction "2_2") (pintype "passive"))
      (node (ref "C20") (pin "2") (pinfunction "2_2") (pintype "passive"))
      (node (ref "C21") (pin "2") (pinfunction "2_2") (pintype "passive"))
      (node (ref "C22") (pin "2") (pinfunction "2_2") (pintype "passive"))
      (node (ref "C23") (pin "2") (pinfunction "2_2") (pintype "passive"))
      (node (ref "C7") (pin "2") (pinfunction "2_2") (pintype "passive"))
      (node (ref "C8") (pin "2") (pinfunction "2_2") (pintype "passive"))
      (node (ref "DA1") (pin "10") (pinfunction "VA33_AFE_10") (pintype "power_in"))
      (node (ref "DA1") (pin "12") (pinfunction "VA33_PA_12") (pintype "power_in"))
      (node (ref "DA1") (pin "14") (pinfunction "VA33_TR_14") (pintype "power_in"))
      (node (ref "DA1") (pin "16") (pinfunction "VDDIO_EC_16") (pintype "power_in"))
      (node (ref "DA1") (pin "23") (pinfunction "VA33_SYS_23") (pintype "power_in"))
      (node (ref "DA1") (pin "26") (pinfunction "VD33IO_26") (pintype "power_in"))
      (node (ref "DA1") (pin "30") (pinfunction "VDIO_SDIO_30") (pintype "power_in"))
      (node (ref "DA1") (pin "35") (pinfunction "VD33IO_35") (pintype "power_in"))
      (node (ref "DA1") (pin "36") (pinfunction "SW_HV3_36") (pintype "power_in"))
      (node (ref "DA1") (pin "39") (pinfunction "VD33_IN_39") (pintype "power_in"))
      (node (ref "DA1") (pin "4") (pinfunction "VD33IO_4") (pintype "power_in"))
      (node (ref "DA1") (pin "45") (pinfunction "VDDIO_EC_45") (pintype "power_in"))
      (node (ref "R2") (pin "2") (pinfunction "2_2") (pintype "passive"))
      (node (ref "R3") (pin "2") (pinfunction "2_2") (pintype "passive"))
      (node (ref "R5") (pin "2") (pinfunction "2_2") (pintype "passive"))
      (node (ref "XS8") (pin "1") (pinfunction "1_1") (pintype "passive"))
    )
    (net (code "36") (name "unconnected-(DA1A-NFC_IN-Pad6)") (class "Default")
      (node (ref "DA1") (pin "6") (pinfunction "NFC_IN_6") (pintype "bidirectional+no_connect"))
    )
    (net (code "37") (name "unconnected-(DA1A-NFC_IP-Pad5)") (class "Default")
      (node (ref "DA1") (pin "5") (pinfunction "NFC_IP_5") (pintype "bidirectional+no_connect"))
    )
  )
)
